# utorch.net
KiCad netlist of a schematic drawn in EAGLE
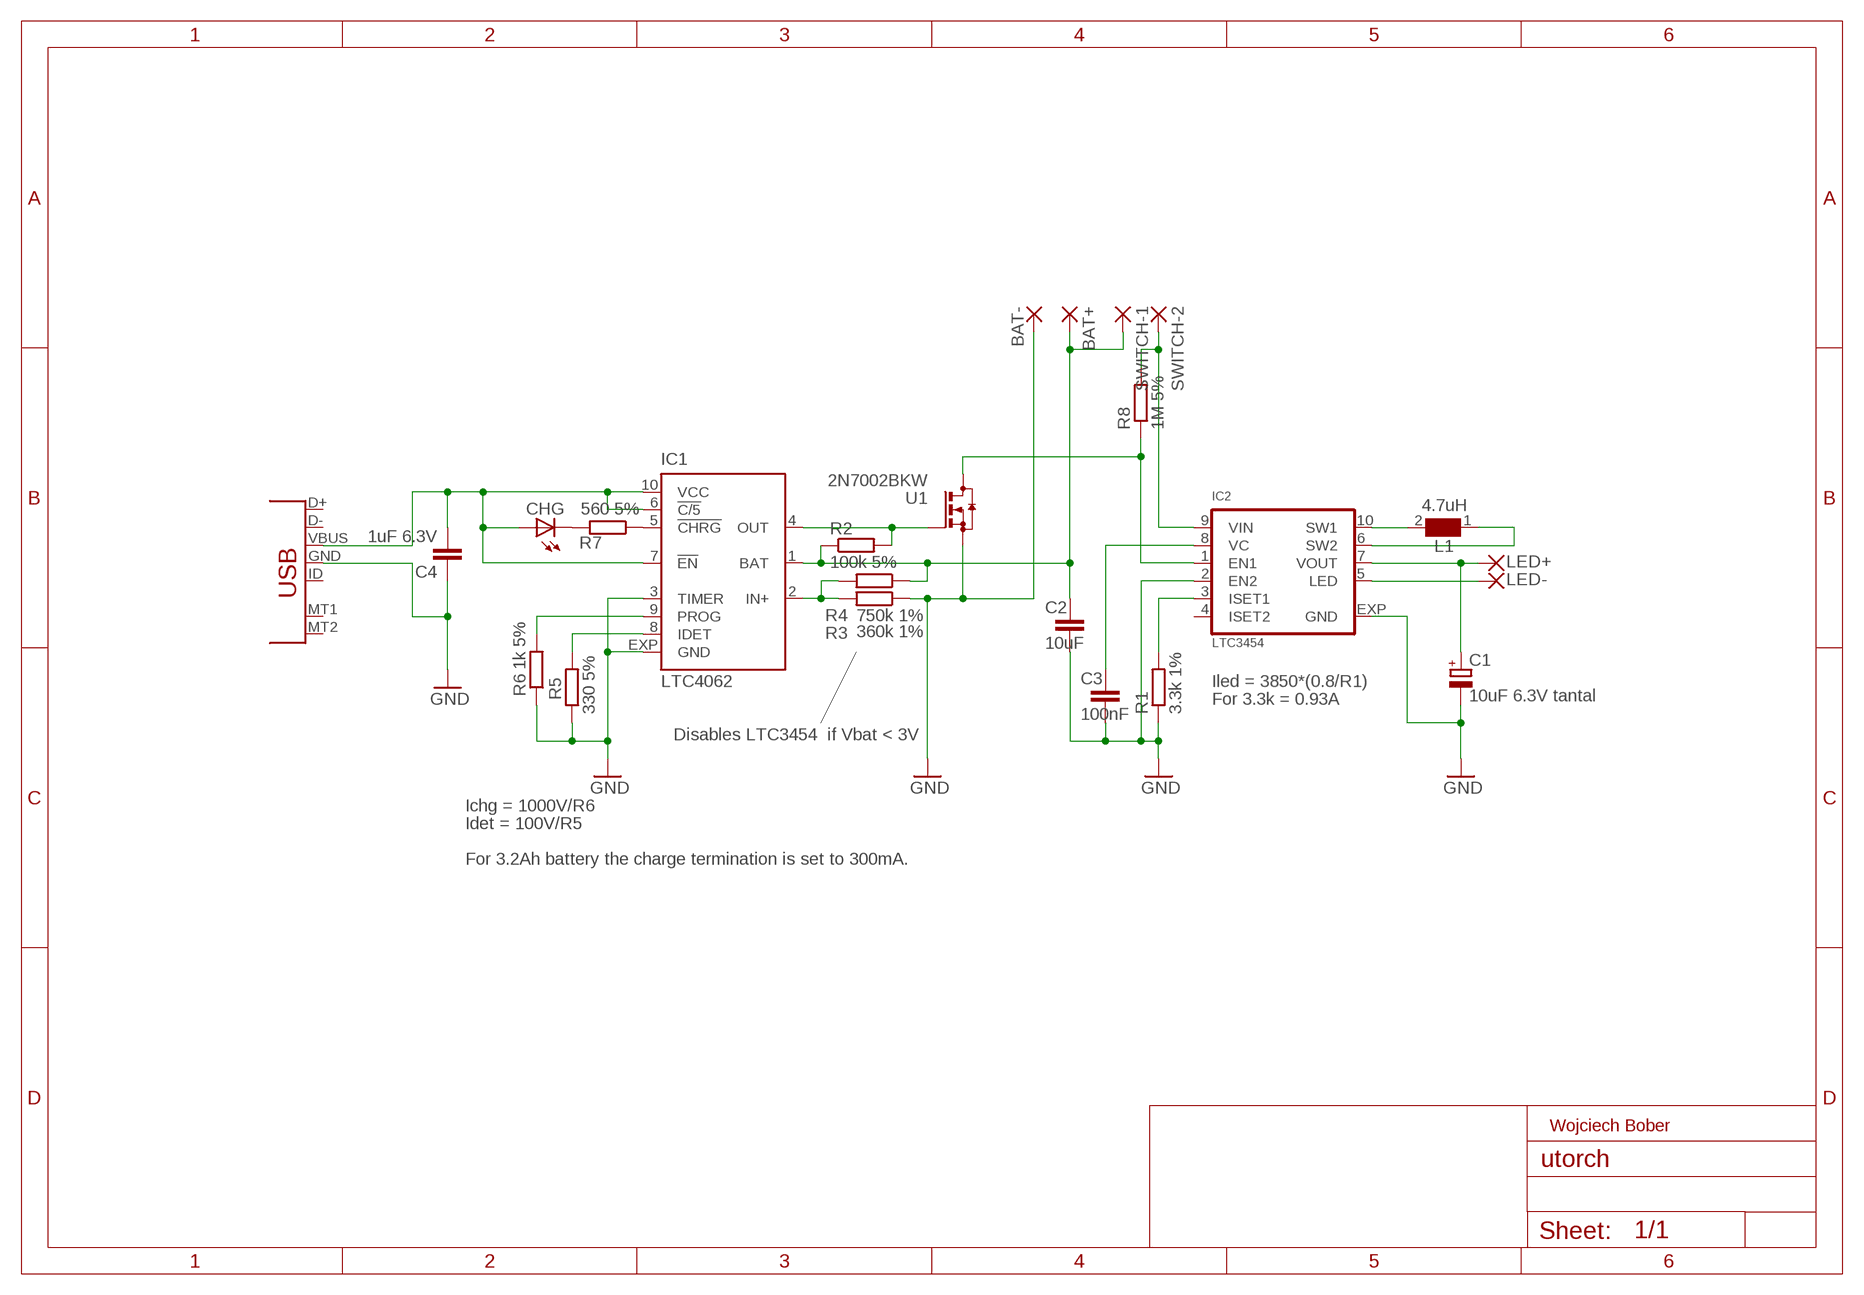
[diagram p0: schematic, sheet 1]

(export (version "E")
  (design (tool "Eeschema 10.0.6"))
  (components
    (comp (ref "BAT+")
      (value "WIREPAD1,6/0,8")
      (footprint "eagle-import:1,6_0,8")
      (libsource (lib "eagle-import") (part "WIREPAD1,6/0,8"))
    )
    (comp (ref "BAT-")
      (value "WIREPAD1,6/0,8")
      (footprint "eagle-import:1,6_0,8")
      (libsource (lib "eagle-import") (part "WIREPAD1,6/0,8"))
    )
    (comp (ref "C1")
      (value "10uF 6.3V tantal")
      (footprint "eagle-import:SMC_A")
      (libsource (lib "eagle-import") (part "CPOL-EUSMCA"))
    )
    (comp (ref "C2")
      (value "10uF")
      (footprint "eagle-import:C0603")
      (libsource (lib "eagle-import") (part "rcl_C-EUC0603"))
    )
    (comp (ref "C3")
      (value "100nF")
      (footprint "eagle-import:ADL_LIB_001_C0402")
      (libsource (lib "eagle-import") (part "C-EUC0402"))
    )
    (comp (ref "C4")
      (value "1uF 6.3V")
      (footprint "eagle-import:ADL_LIB_001_C0402")
      (libsource (lib "eagle-import") (part "C-EUC0402"))
    )
    (comp (ref "CHG")
      (value "LEDCHIP-LED0603")
      (footprint "eagle-import:CHIP-LED0603")
      (libsource (lib "eagle-import") (part "LEDCHIP-LED0603"))
    )
    (comp (ref "IC1")
      (value "LTC4062")
      (footprint "eagle-import:DFN10-3X3")
      (fields (field (name "MPN") "LTC4062EDD#PBF"))
      (libsource (lib "eagle-import") (part "LTC4062"))
    )
    (comp (ref "IC2")
      (value "LTC3454")
      (footprint "eagle-import:DFN10-3X3")
      (libsource (lib "eagle-import") (part "LTC3454"))
    )
    (comp (ref "L1")
      (value "4.7uH")
      (footprint "eagle-import:WE-MAPI_2510")
      (libsource (lib "eagle-import") (part "WE-MAPI2510"))
    )
    (comp (ref "LED+")
      (value "WIREPAD1,6/0,8")
      (footprint "eagle-import:1,6_0,8")
      (libsource (lib "eagle-import") (part "WIREPAD1,6/0,8"))
    )
    (comp (ref "LED-")
      (value "WIREPAD1,6/0,8")
      (footprint "eagle-import:1,6_0,8")
      (libsource (lib "eagle-import") (part "WIREPAD1,6/0,8"))
    )
    (comp (ref "R1")
      (value "3.3k 1%")
      (footprint "eagle-import:ADL_LIB_001_R0402")
      (libsource (lib "eagle-import") (part "R-EU_R0402"))
    )
    (comp (ref "R2")
      (value "100k 5%")
      (footprint "eagle-import:ADL_LIB_001_R0402")
      (libsource (lib "eagle-import") (part "R-EU_R0402"))
    )
    (comp (ref "R3")
      (value "360k 1%")
      (footprint "eagle-import:ADL_LIB_001_R0402")
      (libsource (lib "eagle-import") (part "R-EU_R0402"))
    )
    (comp (ref "R4")
      (value "750k 1%")
      (footprint "eagle-import:ADL_LIB_001_R0402")
      (libsource (lib "eagle-import") (part "R-EU_R0402"))
    )
    (comp (ref "R5")
      (value "330 5%")
      (footprint "eagle-import:R0402")
      (libsource (lib "eagle-import") (part "resistor_R-EU_R0402"))
    )
    (comp (ref "R6")
      (value "1k 5%")
      (footprint "eagle-import:R0402")
      (libsource (lib "eagle-import") (part "resistor_R-EU_R0402"))
    )
    (comp (ref "R7")
      (value "560 5%")
      (footprint "eagle-import:R0402")
      (libsource (lib "eagle-import") (part "resistor_R-EU_R0402"))
    )
    (comp (ref "R8")
      (value "1M 5%")
      (footprint "eagle-import:ADL_LIB_001_R0402")
      (libsource (lib "eagle-import") (part "R-EU_R0402"))
    )
    (comp (ref "SWITCH-1")
      (value "WIREPAD1,6/0,8")
      (footprint "eagle-import:1,6_0,8")
      (libsource (lib "eagle-import") (part "WIREPAD1,6/0,8"))
    )
    (comp (ref "SWITCH-2")
      (value "WIREPAD1,6/0,8")
      (footprint "eagle-import:1,6_0,8")
      (libsource (lib "eagle-import") (part "WIREPAD1,6/0,8"))
    )
    (comp (ref "U1")
      (value "2N7002BKW")
      (footprint "eagle-import:SOT323")
      (libsource (lib "eagle-import") (part "2N7002BKW"))
    )
    (comp (ref "X1")
      (value "USB-MICROB")
      (footprint "eagle-import:USB-MICROB")
      (libsource (lib "eagle-import") (part "USB-MICROB"))
    )
  )
  (nets
    (net (code "1") (name "GND") (class "Default")
      (node (ref "BAT-") (pin "1") (pinfunction "P_1") (pintype "passive"))
      (node (ref "C1") (pin "-") (pinfunction "-_-") (pintype "passive"))
      (node (ref "C2") (pin "2") (pinfunction "2_2") (pintype "passive"))
      (node (ref "C3") (pin "1") (pinfunction "1_1") (pintype "passive"))
      (node (ref "C4") (pin "1") (pinfunction "1_1") (pintype "passive"))
      (node (ref "IC1") (pin "3") (pinfunction "TIMER_3") (pintype "passive"))
      (node (ref "IC1") (pin "EXP") (pinfunction "GND_EXP") (pintype "power_in"))
      (node (ref "IC2") (pin "2") (pinfunction "EN2_2") (pintype "bidirectional"))
      (node (ref "IC2") (pin "EXP") (pinfunction "GND_EXP") (pintype "bidirectional"))
      (node (ref "R1") (pin "1") (pinfunction "1_1") (pintype "passive"))
      (node (ref "R3") (pin "1") (pinfunction "1_1") (pintype "passive"))
      (node (ref "R5") (pin "1") (pinfunction "1_1") (pintype "passive"))
      (node (ref "R6") (pin "1") (pinfunction "1_1") (pintype "passive"))
      (node (ref "U1") (pin "2") (pinfunction "S_2") (pintype "passive"))
      (node (ref "X1") (pin "GND") (pinfunction "GND_GND") (pintype "bidirectional"))
    )
    (net (code "2") (name "Net-(BAT+-P)") (class "Default")
      (node (ref "BAT+") (pin "1") (pinfunction "P_1") (pintype "passive"))
      (node (ref "C2") (pin "1") (pinfunction "1_1") (pintype "passive"))
      (node (ref "IC1") (pin "1") (pinfunction "BAT_1") (pintype "passive"))
      (node (ref "R2") (pin "1") (pinfunction "1_1") (pintype "passive"))
      (node (ref "R4") (pin "1") (pinfunction "1_1") (pintype "passive"))
      (node (ref "SWITCH-1") (pin "1") (pinfunction "P_1") (pintype "passive"))
    )
    (net (code "3") (name "Net-(CHG-PadC)") (class "Default")
      (node (ref "CHG") (pin "C") (pinfunction "C_C") (pintype "passive"))
      (node (ref "R7") (pin "2") (pinfunction "2_2") (pintype "passive"))
    )
    (net (code "4") (name "Net-(IC1-IDET)") (class "Default")
      (node (ref "IC1") (pin "8") (pinfunction "IDET_8") (pintype "passive"))
      (node (ref "R5") (pin "2") (pinfunction "2_2") (pintype "passive"))
    )
    (net (code "5") (name "Net-(IC1-IN+)") (class "Default")
      (node (ref "IC1") (pin "2") (pinfunction "IN+_2") (pintype "input"))
      (node (ref "R3") (pin "2") (pinfunction "2_2") (pintype "passive"))
      (node (ref "R4") (pin "2") (pinfunction "2_2") (pintype "passive"))
    )
    (net (code "6") (name "Net-(IC1-OUT)") (class "Default")
      (node (ref "IC1") (pin "4") (pinfunction "OUT_4") (pintype "open_collector"))
      (node (ref "R2") (pin "2") (pinfunction "2_2") (pintype "passive"))
      (node (ref "U1") (pin "1") (pinfunction "G_1") (pintype "passive"))
    )
    (net (code "7") (name "Net-(IC1-PROG)") (class "Default")
      (node (ref "IC1") (pin "9") (pinfunction "PROG_9") (pintype "passive"))
      (node (ref "R6") (pin "2") (pinfunction "2_2") (pintype "passive"))
    )
    (net (code "8") (name "Net-(IC1-VCC)") (class "Default")
      (node (ref "C4") (pin "2") (pinfunction "2_2") (pintype "passive"))
      (node (ref "CHG") (pin "A") (pinfunction "A_A") (pintype "passive"))
      (node (ref "IC1") (pin "10") (pinfunction "VCC_10") (pintype "power_in"))
      (node (ref "IC1") (pin "6") (pinfunction "~{C/5}_6") (pintype "input"))
      (node (ref "IC1") (pin "7") (pinfunction "~{EN}_7") (pintype "input"))
      (node (ref "X1") (pin "VBUS") (pinfunction "VBUS_VBUS") (pintype "bidirectional"))
    )
    (net (code "9") (name "Net-(IC1-~{CHRG})") (class "Default")
      (node (ref "IC1") (pin "5") (pinfunction "~{CHRG}_5") (pintype "open_collector"))
      (node (ref "R7") (pin "1") (pinfunction "1_1") (pintype "passive"))
    )
    (net (code "10") (name "Net-(IC2-EN1)") (class "Default")
      (node (ref "IC2") (pin "1") (pinfunction "EN1_1") (pintype "bidirectional"))
      (node (ref "R8") (pin "1") (pinfunction "1_1") (pintype "passive"))
      (node (ref "U1") (pin "3") (pinfunction "D_3") (pintype "passive"))
    )
    (net (code "11") (name "Net-(IC2-ISET1)") (class "Default")
      (node (ref "IC2") (pin "3") (pinfunction "ISET1_3") (pintype "bidirectional"))
      (node (ref "R1") (pin "2") (pinfunction "2_2") (pintype "passive"))
    )
    (net (code "12") (name "Net-(IC2-LED)") (class "Default")
      (node (ref "IC2") (pin "5") (pinfunction "LED_5") (pintype "bidirectional"))
      (node (ref "LED-") (pin "1") (pinfunction "P_1") (pintype "passive"))
    )
    (net (code "13") (name "Net-(IC2-SW1)") (class "Default")
      (node (ref "IC2") (pin "10") (pinfunction "SW1_10") (pintype "bidirectional"))
      (node (ref "L1") (pin "2") (pinfunction "2_2") (pintype "passive"))
    )
    (net (code "14") (name "Net-(IC2-SW2)") (class "Default")
      (node (ref "IC2") (pin "6") (pinfunction "SW2_6") (pintype "bidirectional"))
      (node (ref "L1") (pin "1") (pinfunction "1_1") (pintype "passive"))
    )
    (net (code "15") (name "Net-(IC2-VC)") (class "Default")
      (node (ref "C3") (pin "2") (pinfunction "2_2") (pintype "passive"))
      (node (ref "IC2") (pin "8") (pinfunction "VC_8") (pintype "bidirectional"))
    )
    (net (code "16") (name "Net-(IC2-VIN)") (class "Default")
      (node (ref "IC2") (pin "9") (pinfunction "VIN_9") (pintype "bidirectional"))
      (node (ref "R8") (pin "2") (pinfunction "2_2") (pintype "passive"))
      (node (ref "SWITCH-2") (pin "1") (pinfunction "P_1") (pintype "passive"))
    )
    (net (code "17") (name "Net-(IC2-VOUT)") (class "Default")
      (node (ref "C1") (pin "+") (pinfunction "+_+") (pintype "passive"))
      (node (ref "IC2") (pin "7") (pinfunction "VOUT_7") (pintype "bidirectional"))
      (node (ref "LED+") (pin "1") (pinfunction "P_1") (pintype "passive"))
    )
    (net (code "18") (name "unconnected-(IC2-ISET2-Pad4)") (class "Default")
      (node (ref "IC2") (pin "4") (pinfunction "ISET2_4") (pintype "bidirectional"))
    )
    (net (code "19") (name "unconnected-(X1-PadD+)") (class "Default")
      (node (ref "X1") (pin "D+") (pinfunction "D+_D+") (pintype "bidirectional"))
    )
    (net (code "20") (name "unconnected-(X1-PadD-)") (class "Default")
      (node (ref "X1") (pin "D-") (pinfunction "D-_D-") (pintype "bidirectional"))
    )
    (net (code "21") (name "unconnected-(X1-PadID)") (class "Default")
      (node (ref "X1") (pin "ID") (pinfunction "ID_ID") (pintype "bidirectional"))
    )
    (net (code "22") (name "unconnected-(X1-PadMT1)") (class "Default")
      (node (ref "X1") (pin "MT1") (pinfunction "MT1_MT1") (pintype "bidirectional"))
    )
    (net (code "23") (name "unconnected-(X1-PadMT2)") (class "Default")
      (node (ref "X1") (pin "MT2") (pinfunction "MT2_MT2") (pintype "bidirectional"))
    )
  )
)
